# uC.net
KiCad netlist of a schematic drawn in Altium Designer
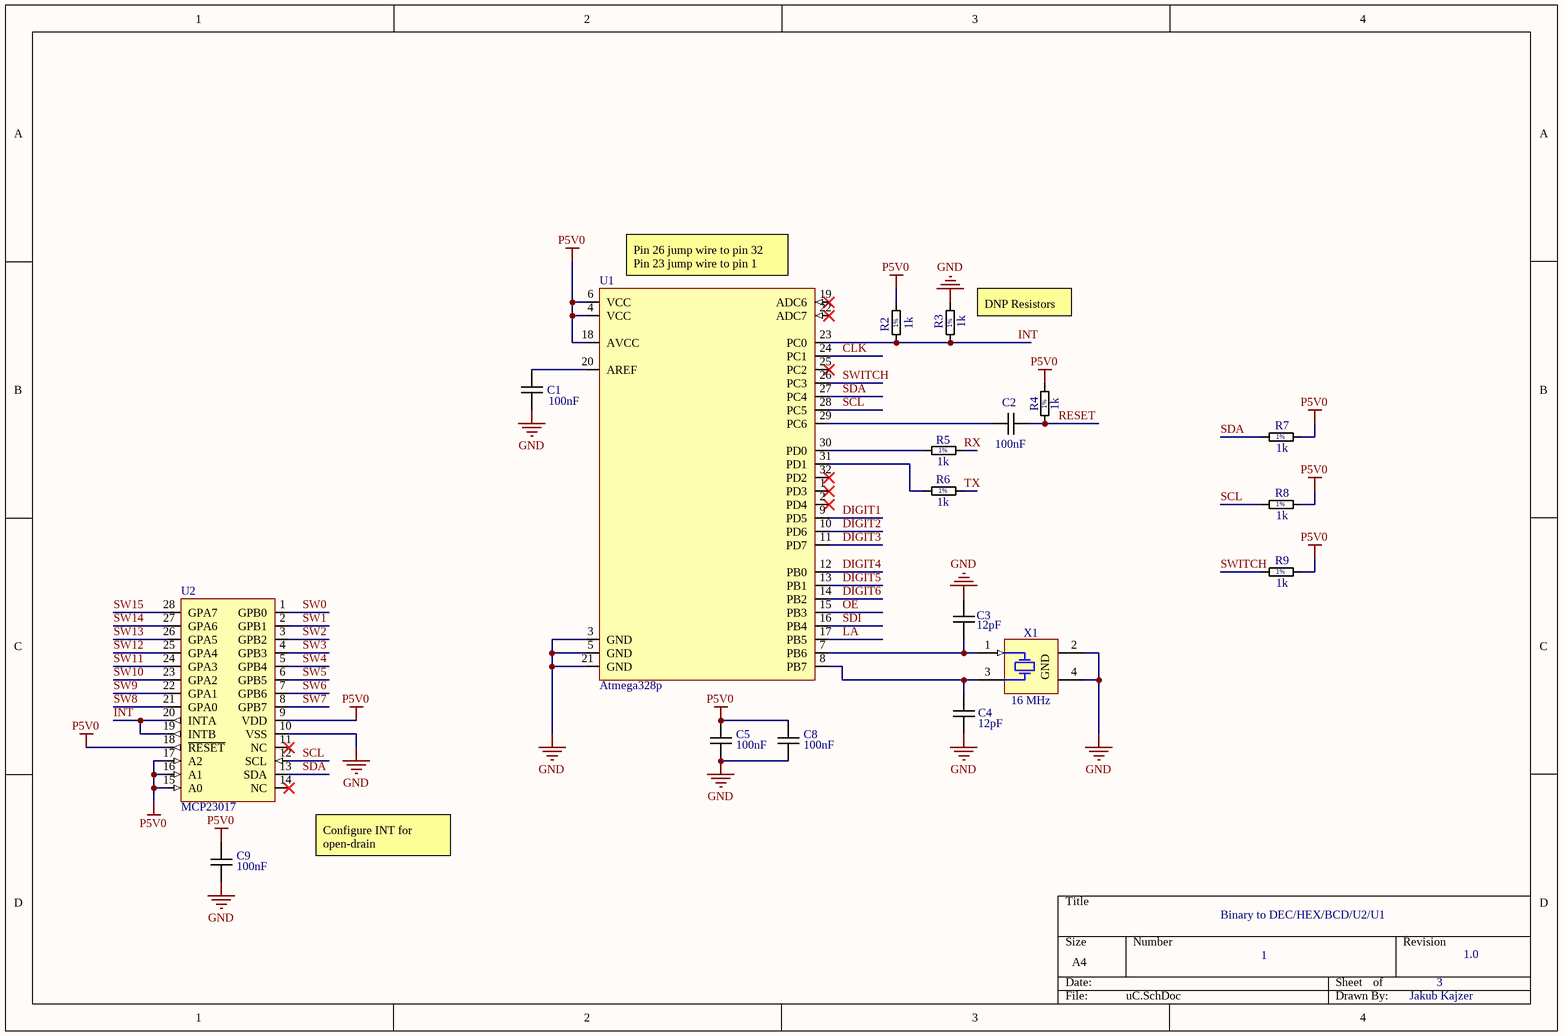
[diagram p0: uC.SchDoc]

(export (version "E")
  (design (tool "Eeschema 10.0.6"))
  (components
    (comp (ref "C1")
      (value "100nF")
      (footprint "CAPC0402X60N")
      (description "Non-polarised capacitor")
      (fields
        (field (name "MANUFACTURER") "GENERIC")
        (field (name "MANUFACTURER PART NUMBER") "CC0402_100NF_16V_10%_X7R")
        (field (name "AUTHOR") "KB")
      )
      (libsource (lib "Capacitors") (part "Capacitor - non polarized"))
    )
    (comp (ref "C2")
      (value "100nF")
      (footprint "CAPC0402X60N")
      (description "Non-polarised capacitor")
      (fields
        (field (name "MANUFACTURER") "GENERIC")
        (field (name "MANUFACTURER PART NUMBER") "CC0402_100NF_16V_10%_X7R")
        (field (name "AUTHOR") "KB")
      )
      (libsource (lib "Capacitors") (part "Capacitor - non polarized"))
    )
    (comp (ref "C3")
      (value "12pF")
      (footprint "CAPC0402X60N")
      (description "Non-polarised capacitor")
      (fields
        (field (name "MANUFACTURER") "GENERIC")
        (field (name "MANUFACTURER PART NUMBER") "CC0402_12PF_50V_5%_C0G")
        (field (name "AUTHOR") "KB")
      )
      (libsource (lib "Capacitors") (part "Capacitor - non polarized"))
    )
    (comp (ref "C4")
      (value "12pF")
      (footprint "CAPC0402X60N")
      (description "Non-polarised capacitor")
      (fields
        (field (name "MANUFACTURER") "GENERIC")
        (field (name "MANUFACTURER PART NUMBER") "CC0402_12PF_50V_5%_C0G")
        (field (name "AUTHOR") "KB")
      )
      (libsource (lib "Capacitors") (part "Capacitor - non polarized"))
    )
    (comp (ref "C5")
      (value "100nF")
      (footprint "CAPC0402X60N")
      (description "Non-polarised capacitor")
      (fields
        (field (name "MANUFACTURER") "GENERIC")
        (field (name "MANUFACTURER PART NUMBER") "CC0402_100NF_16V_10%_X7R")
        (field (name "AUTHOR") "KB")
      )
      (libsource (lib "Capacitors") (part "Capacitor - non polarized"))
    )
    (comp (ref "C8")
      (value "100nF")
      (footprint "CAPC0402X60N")
      (description "Non-polarised capacitor")
      (fields
        (field (name "MANUFACTURER") "GENERIC")
        (field (name "MANUFACTURER PART NUMBER") "CC0402_100NF_16V_10%_X7R")
        (field (name "AUTHOR") "KB")
      )
      (libsource (lib "Capacitors") (part "Capacitor - non polarized"))
    )
    (comp (ref "C9")
      (value "100nF")
      (footprint "CAPC0402X60N")
      (description "Non-polarised capacitor")
      (fields
        (field (name "MANUFACTURER") "GENERIC")
        (field (name "MANUFACTURER PART NUMBER") "CC0402_100NF_16V_10%_X7R")
        (field (name "AUTHOR") "KB")
      )
      (libsource (lib "Capacitors") (part "Capacitor - non polarized"))
    )
    (comp (ref "R2")
      (value "1k")
      (footprint "RESC0402X40N")
      (description "General Purpose Thick Film Chip Resistor")
      (fields
        (field (name "MANUFACTURER") "GENERIC")
        (field (name "MANUFACTURER PART NUMBER") "R0402_1K00_0.0625W 0.1W 0.125W 0.25W 0.5W 1W 0.75W 1W_100PPM")
        (field (name "AUTHOR") "KB")
      )
      (libsource (lib "Resistors") (part "Resistor - 1%"))
    )
    (comp (ref "R3")
      (value "1k")
      (footprint "RESC0402X40N")
      (description "General Purpose Thick Film Chip Resistor")
      (fields
        (field (name "MANUFACTURER") "GENERIC")
        (field (name "MANUFACTURER PART NUMBER") "R0402_1K00_0.0625W 0.1W 0.125W 0.25W 0.5W 1W 0.75W 1W_100PPM")
        (field (name "AUTHOR") "KB")
      )
      (libsource (lib "Resistors") (part "Resistor - 1%"))
    )
    (comp (ref "R4")
      (value "1k")
      (footprint "RESC0402X40N")
      (description "General Purpose Thick Film Chip Resistor")
      (fields
        (field (name "MANUFACTURER") "GENERIC")
        (field (name "MANUFACTURER PART NUMBER") "R0402_1K00_0.0625W 0.1W 0.125W 0.25W 0.5W 1W 0.75W 1W_100PPM")
        (field (name "AUTHOR") "KB")
      )
      (libsource (lib "Resistors") (part "Resistor - 1%"))
    )
    (comp (ref "R5")
      (value "1k")
      (footprint "RESC0402X40N")
      (description "General Purpose Thick Film Chip Resistor")
      (fields
        (field (name "MANUFACTURER") "GENERIC")
        (field (name "MANUFACTURER PART NUMBER") "R0402_1K00_0.0625W 0.1W 0.125W 0.25W 0.5W 1W 0.75W 1W_100PPM")
        (field (name "AUTHOR") "KB")
      )
      (libsource (lib "Resistors") (part "Resistor - 1%"))
    )
    (comp (ref "R6")
      (value "1k")
      (footprint "RESC0402X40N")
      (description "General Purpose Thick Film Chip Resistor")
      (fields
        (field (name "MANUFACTURER") "GENERIC")
        (field (name "MANUFACTURER PART NUMBER") "R0402_1K00_0.0625W 0.1W 0.125W 0.25W 0.5W 1W 0.75W 1W_100PPM")
        (field (name "AUTHOR") "KB")
      )
      (libsource (lib "Resistors") (part "Resistor - 1%"))
    )
    (comp (ref "R7")
      (value "1k")
      (footprint "RESC0402X40N")
      (description "General Purpose Thick Film Chip Resistor")
      (fields
        (field (name "MANUFACTURER") "GENERIC")
        (field (name "MANUFACTURER PART NUMBER") "R0402_1K00_0.0625W 0.1W 0.125W 0.25W 0.5W 1W 0.75W 1W_100PPM")
        (field (name "AUTHOR") "KB")
      )
      (libsource (lib "Resistors") (part "Resistor - 1%"))
    )
    (comp (ref "R8")
      (value "1k")
      (footprint "RESC0402X40N")
      (description "General Purpose Thick Film Chip Resistor")
      (fields
        (field (name "MANUFACTURER") "GENERIC")
        (field (name "MANUFACTURER PART NUMBER") "R0402_1K00_0.0625W 0.1W 0.125W 0.25W 0.5W 1W 0.75W 1W_100PPM")
        (field (name "AUTHOR") "KB")
      )
      (libsource (lib "Resistors") (part "Resistor - 1%"))
    )
    (comp (ref "R9")
      (value "1k")
      (footprint "RESC0402X40N")
      (description "General Purpose Thick Film Chip Resistor")
      (fields
        (field (name "MANUFACTURER") "GENERIC")
        (field (name "MANUFACTURER PART NUMBER") "R0402_1K00_0.0625W 0.1W 0.125W 0.25W 0.5W 1W 0.75W 1W_100PPM")
        (field (name "AUTHOR") "KB")
      )
      (libsource (lib "Resistors") (part "Resistor - 1%"))
    )
    (comp (ref "U1")
      (value "Atmega328p")
      (footprint "STM-LQFP32_N")
      (description "8-bit AVR Microcontroller with 32K Bytes In-SystemProgrammable Flash")
      (fields (field (name "MANUFACTURER 1 PART NUMBER") "ATMEGA328PB-AU") (field (name "AUTHOR") "JK"))
      (libsource (lib "ICs And Semiconductors") (part "Atmega328p"))
    )
    (comp (ref "U2")
      (value "MCP23017")
      (footprint "SSOP28")
      (description "16-Bit I/O Expander with Serial Interface")
      (fields (field (name "MANUFACTURER 1 PART NUMBER") "MCP23017-E/SS") (field (name "AUTHOR") "JK"))
      (libsource (lib "ICs And Semiconductors") (part "MCP23017"))
    )
    (comp (ref "X1")
      (value "16 MHz")
      (footprint "LFXTAL069392CUTT")
      (description "ˇĹ0ppm 10pF -40°C to +85°C  4 Pins, 2.5x2X0.6mm")
      (fields (field (name "MANUFACTURER 1 PART NUMBER") "LFXTAL069392CUTT") (field (name "AUTHOR") "PC"))
      (libsource (lib "ICs And Semiconductors") (part "Quartz Crystal 1X 2GND 3X 4GND"))
    )
  )
  (nets
    (net (code "1") (name "/CLK") (class "Default")
      (node (ref "U1") (pin "24") (pinfunction "PC1_24") (pintype "bidirectional"))
    )
    (net (code "2") (name "/DIGIT1") (class "Default")
      (node (ref "U1") (pin "9") (pinfunction "PD5_9") (pintype "bidirectional"))
    )
    (net (code "3") (name "/DIGIT2") (class "Default")
      (node (ref "U1") (pin "10") (pinfunction "PD6_10") (pintype "bidirectional"))
    )
    (net (code "4") (name "/DIGIT3") (class "Default")
      (node (ref "U1") (pin "11") (pinfunction "PD7_11") (pintype "bidirectional"))
    )
    (net (code "5") (name "/DIGIT4") (class "Default")
      (node (ref "U1") (pin "12") (pinfunction "PB0_12") (pintype "bidirectional"))
    )
    (net (code "6") (name "/DIGIT5") (class "Default")
      (node (ref "U1") (pin "13") (pinfunction "PB1_13") (pintype "bidirectional"))
    )
    (net (code "7") (name "/DIGIT6") (class "Default")
      (node (ref "U1") (pin "14") (pinfunction "PB2_14") (pintype "bidirectional"))
    )
    (net (code "8") (name "/INT") (class "Default")
      (node (ref "R2") (pin "1") (pinfunction "1_1") (pintype "passive"))
      (node (ref "R3") (pin "1") (pinfunction "1_1") (pintype "passive"))
      (node (ref "U1") (pin "23") (pinfunction "PC0_23") (pintype "bidirectional"))
      (node (ref "U2") (pin "19") (pinfunction "INTB_19") (pintype "output"))
      (node (ref "U2") (pin "20") (pinfunction "INTA_20") (pintype "output"))
    )
    (net (code "9") (name "/LA") (class "Default")
      (node (ref "U1") (pin "17") (pinfunction "PB5_17") (pintype "bidirectional"))
    )
    (net (code "10") (name "/OE") (class "Default")
      (node (ref "U1") (pin "15") (pinfunction "PB3_15") (pintype "bidirectional"))
    )
    (net (code "11") (name "/RESET") (class "Default")
      (node (ref "C2") (pin "2") (pinfunction "2_2") (pintype "passive"))
      (node (ref "R4") (pin "1") (pinfunction "1_1") (pintype "passive"))
    )
    (net (code "12") (name "/RX") (class "Default")
      (node (ref "R5") (pin "2") (pinfunction "2_2") (pintype "passive"))
    )
    (net (code "13") (name "/SCL") (class "Default")
      (node (ref "R8") (pin "1") (pinfunction "1_1") (pintype "passive"))
      (node (ref "U1") (pin "28") (pinfunction "PC5_28") (pintype "bidirectional"))
      (node (ref "U2") (pin "12") (pinfunction "SCL_12") (pintype "input"))
    )
    (net (code "14") (name "/SDA") (class "Default")
      (node (ref "R7") (pin "1") (pinfunction "1_1") (pintype "passive"))
      (node (ref "U1") (pin "27") (pinfunction "PC4_27") (pintype "bidirectional"))
      (node (ref "U2") (pin "13") (pinfunction "SDA_13") (pintype "bidirectional"))
    )
    (net (code "15") (name "/SDI") (class "Default")
      (node (ref "U1") (pin "16") (pinfunction "PB4_16") (pintype "bidirectional"))
    )
    (net (code "16") (name "/SW0") (class "Default")
      (node (ref "U2") (pin "1") (pinfunction "GPB0_1") (pintype "bidirectional"))
    )
    (net (code "17") (name "/SW1") (class "Default")
      (node (ref "U2") (pin "2") (pinfunction "GPB1_2") (pintype "bidirectional"))
    )
    (net (code "18") (name "/SW2") (class "Default")
      (node (ref "U2") (pin "3") (pinfunction "GPB2_3") (pintype "bidirectional"))
    )
    (net (code "19") (name "/SW3") (class "Default")
      (node (ref "U2") (pin "4") (pinfunction "GPB3_4") (pintype "bidirectional"))
    )
    (net (code "20") (name "/SW4") (class "Default")
      (node (ref "U2") (pin "5") (pinfunction "GPB4_5") (pintype "bidirectional"))
    )
    (net (code "21") (name "/SW5") (class "Default")
      (node (ref "U2") (pin "6") (pinfunction "GPB5_6") (pintype "bidirectional"))
    )
    (net (code "22") (name "/SW6") (class "Default")
      (node (ref "U2") (pin "7") (pinfunction "GPB6_7") (pintype "bidirectional"))
    )
    (net (code "23") (name "/SW7") (class "Default")
      (node (ref "U2") (pin "8") (pinfunction "GPB7_8") (pintype "bidirectional"))
    )
    (net (code "24") (name "/SW8") (class "Default")
      (node (ref "U2") (pin "21") (pinfunction "GPA0_21") (pintype "bidirectional"))
    )
    (net (code "25") (name "/SW9") (class "Default")
      (node (ref "U2") (pin "22") (pinfunction "GPA1_22") (pintype "bidirectional"))
    )
    (net (code "26") (name "/SW10") (class "Default")
      (node (ref "U2") (pin "23") (pinfunction "GPA2_23") (pintype "bidirectional"))
    )
    (net (code "27") (name "/SW11") (class "Default")
      (node (ref "U2") (pin "24") (pinfunction "GPA3_24") (pintype "bidirectional"))
    )
    (net (code "28") (name "/SW12") (class "Default")
      (node (ref "U2") (pin "25") (pinfunction "GPA4_25") (pintype "bidirectional"))
    )
    (net (code "29") (name "/SW13") (class "Default")
      (node (ref "U2") (pin "26") (pinfunction "GPA5_26") (pintype "bidirectional"))
    )
    (net (code "30") (name "/SW14") (class "Default")
      (node (ref "U2") (pin "27") (pinfunction "GPA6_27") (pintype "bidirectional"))
    )
    (net (code "31") (name "/SW15") (class "Default")
      (node (ref "U2") (pin "28") (pinfunction "GPA7_28") (pintype "bidirectional"))
    )
    (net (code "32") (name "/SWITCH") (class "Default")
      (node (ref "R9") (pin "1") (pinfunction "1_1") (pintype "passive"))
      (node (ref "U1") (pin "26") (pinfunction "PC3_26") (pintype "bidirectional"))
    )
    (net (code "33") (name "/TX") (class "Default")
      (node (ref "R6") (pin "2") (pinfunction "2_2") (pintype "passive"))
    )
    (net (code "34") (name "GND") (class "Default")
      (node (ref "C1") (pin "1") (pinfunction "1_1") (pintype "passive"))
      (node (ref "C3") (pin "2") (pinfunction "2_2") (pintype "passive"))
      (node (ref "C4") (pin "1") (pinfunction "1_1") (pintype "passive"))
      (node (ref "C5") (pin "1") (pinfunction "1_1") (pintype "passive"))
      (node (ref "C8") (pin "1") (pinfunction "1_1") (pintype "passive"))
      (node (ref "C9") (pin "1") (pinfunction "1_1") (pintype "passive"))
      (node (ref "R3") (pin "2") (pinfunction "2_2") (pintype "passive"))
      (node (ref "U1") (pin "21") (pinfunction "GND_21") (pintype "power_in"))
      (node (ref "U1") (pin "3") (pinfunction "GND_3") (pintype "power_in"))
      (node (ref "U1") (pin "5") (pinfunction "GND_5") (pintype "power_in"))
      (node (ref "U2") (pin "10") (pinfunction "VSS_10") (pintype "power_in"))
      (node (ref "X1") (pin "2") (pinfunction "GND_2") (pintype "power_in"))
      (node (ref "X1") (pin "4") (pinfunction "GND_4") (pintype "power_in"))
    )
    (net (code "35") (name "Net-(U1-AREF)") (class "Default")
      (node (ref "C1") (pin "2") (pinfunction "2_2") (pintype "passive"))
      (node (ref "U1") (pin "20") (pinfunction "AREF_20") (pintype "power_in"))
    )
    (net (code "36") (name "Net-(U1-PB6)") (class "Default")
      (node (ref "C3") (pin "1") (pinfunction "1_1") (pintype "passive"))
      (node (ref "U1") (pin "7") (pinfunction "PB6_7") (pintype "bidirectional"))
      (node (ref "X1") (pin "1") (pinfunction "X_1") (pintype "input"))
    )
    (net (code "37") (name "Net-(U1-PB7)") (class "Default")
      (node (ref "C4") (pin "2") (pinfunction "2_2") (pintype "passive"))
      (node (ref "U1") (pin "8") (pinfunction "PB7_8") (pintype "bidirectional"))
      (node (ref "X1") (pin "3") (pinfunction "X_3") (pintype "power_in"))
    )
    (net (code "38") (name "Net-(U1-PC6)") (class "Default")
      (node (ref "C2") (pin "1") (pinfunction "1_1") (pintype "passive"))
      (node (ref "U1") (pin "29") (pinfunction "PC6_29") (pintype "bidirectional"))
    )
    (net (code "39") (name "Net-(U1-PD0)") (class "Default")
      (node (ref "R5") (pin "1") (pinfunction "1_1") (pintype "passive"))
      (node (ref "U1") (pin "30") (pinfunction "PD0_30") (pintype "bidirectional"))
    )
    (net (code "40") (name "Net-(U1-PD1)") (class "Default")
      (node (ref "R6") (pin "1") (pinfunction "1_1") (pintype "passive"))
      (node (ref "U1") (pin "31") (pinfunction "PD1_31") (pintype "bidirectional"))
    )
    (net (code "41") (name "P5V0") (class "Default")
      (node (ref "C5") (pin "2") (pinfunction "2_2") (pintype "passive"))
      (node (ref "C8") (pin "2") (pinfunction "2_2") (pintype "passive"))
      (node (ref "C9") (pin "2") (pinfunction "2_2") (pintype "passive"))
      (node (ref "R2") (pin "2") (pinfunction "2_2") (pintype "passive"))
      (node (ref "R4") (pin "2") (pinfunction "2_2") (pintype "passive"))
      (node (ref "R7") (pin "2") (pinfunction "2_2") (pintype "passive"))
      (node (ref "R8") (pin "2") (pinfunction "2_2") (pintype "passive"))
      (node (ref "R9") (pin "2") (pinfunction "2_2") (pintype "passive"))
      (node (ref "U1") (pin "18") (pinfunction "AVCC_18") (pintype "power_in"))
      (node (ref "U1") (pin "4") (pinfunction "VCC_4") (pintype "power_in"))
      (node (ref "U1") (pin "6") (pinfunction "VCC_6") (pintype "power_in"))
      (node (ref "U2") (pin "15") (pinfunction "A0_15") (pintype "input"))
      (node (ref "U2") (pin "16") (pinfunction "A1_16") (pintype "input"))
      (node (ref "U2") (pin "17") (pinfunction "A2_17") (pintype "input"))
      (node (ref "U2") (pin "18") (pinfunction "~{RESET}_18") (pintype "output"))
      (node (ref "U2") (pin "9") (pinfunction "VDD_9") (pintype "power_in"))
    )
    (net (code "42") (name "unconnected-(U1-ADC6-Pad19)") (class "Default")
      (node (ref "U1") (pin "19") (pinfunction "ADC6_19") (pintype "input+no_connect"))
    )
    (net (code "43") (name "unconnected-(U1-ADC7-Pad22)") (class "Default")
      (node (ref "U1") (pin "22") (pinfunction "ADC7_22") (pintype "input+no_connect"))
    )
    (net (code "44") (name "unconnected-(U1-PC2-Pad25)") (class "Default")
      (node (ref "U1") (pin "25") (pinfunction "PC2_25") (pintype "bidirectional+no_connect"))
    )
    (net (code "45") (name "unconnected-(U1-PD2-Pad32)") (class "Default")
      (node (ref "U1") (pin "32") (pinfunction "PD2_32") (pintype "bidirectional+no_connect"))
    )
    (net (code "46") (name "unconnected-(U1-PD3-Pad1)") (class "Default")
      (node (ref "U1") (pin "1") (pinfunction "PD3_1") (pintype "bidirectional+no_connect"))
    )
    (net (code "47") (name "unconnected-(U1-PD4-Pad2)") (class "Default")
      (node (ref "U1") (pin "2") (pinfunction "PD4_2") (pintype "bidirectional+no_connect"))
    )
    (net (code "48") (name "unconnected-(U2-NC-Pad11)") (class "Default")
      (node (ref "U2") (pin "11") (pinfunction "NC_11") (pintype "passive+no_connect"))
    )
    (net (code "49") (name "unconnected-(U2-NC-Pad14)") (class "Default")
      (node (ref "U2") (pin "14") (pinfunction "NC_14") (pintype "passive+no_connect"))
    )
  )
)
